# S7CAS-PLEIADES-CARTE-MERE_P06_CLOCK.net
KiCad netlist of a schematic drawn in Altium Designer
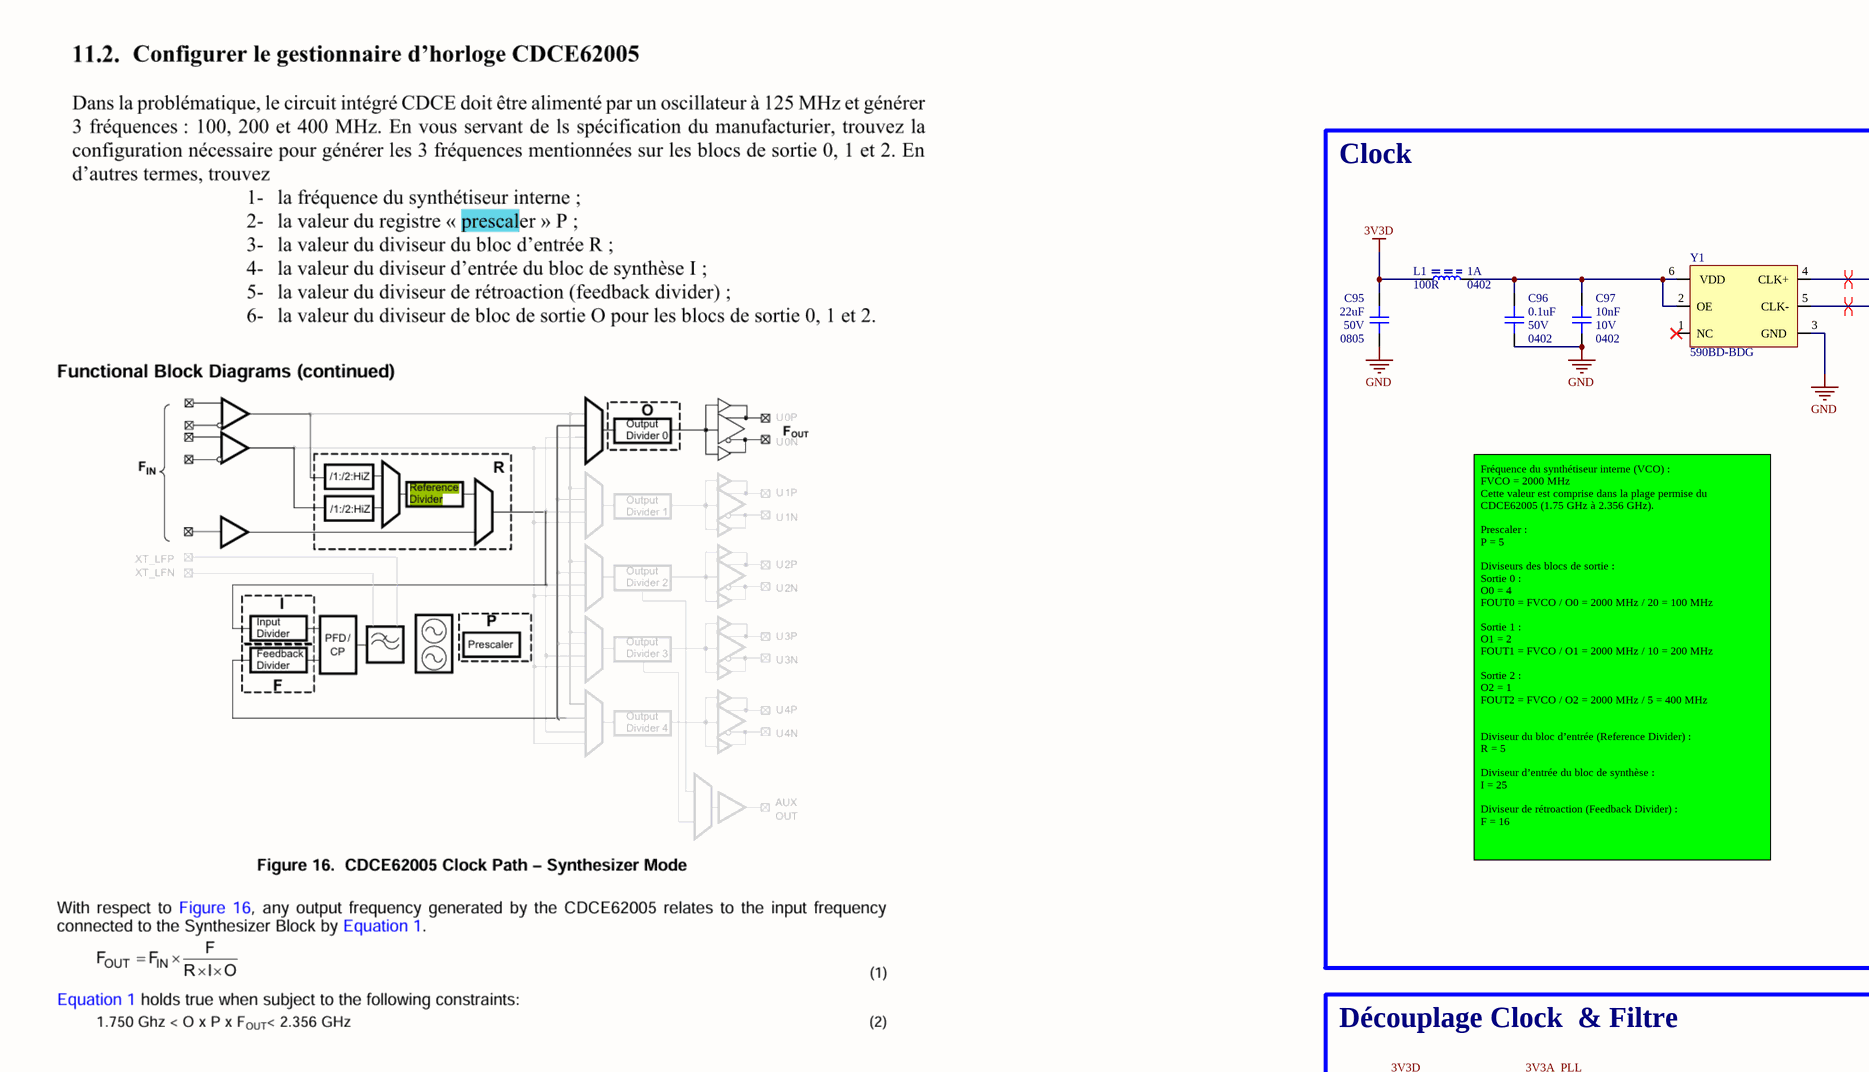
[diagram p0: S7CAS-PLEIADES-CARTE-MERE_P06_CLOCK.SchDoc, top left]
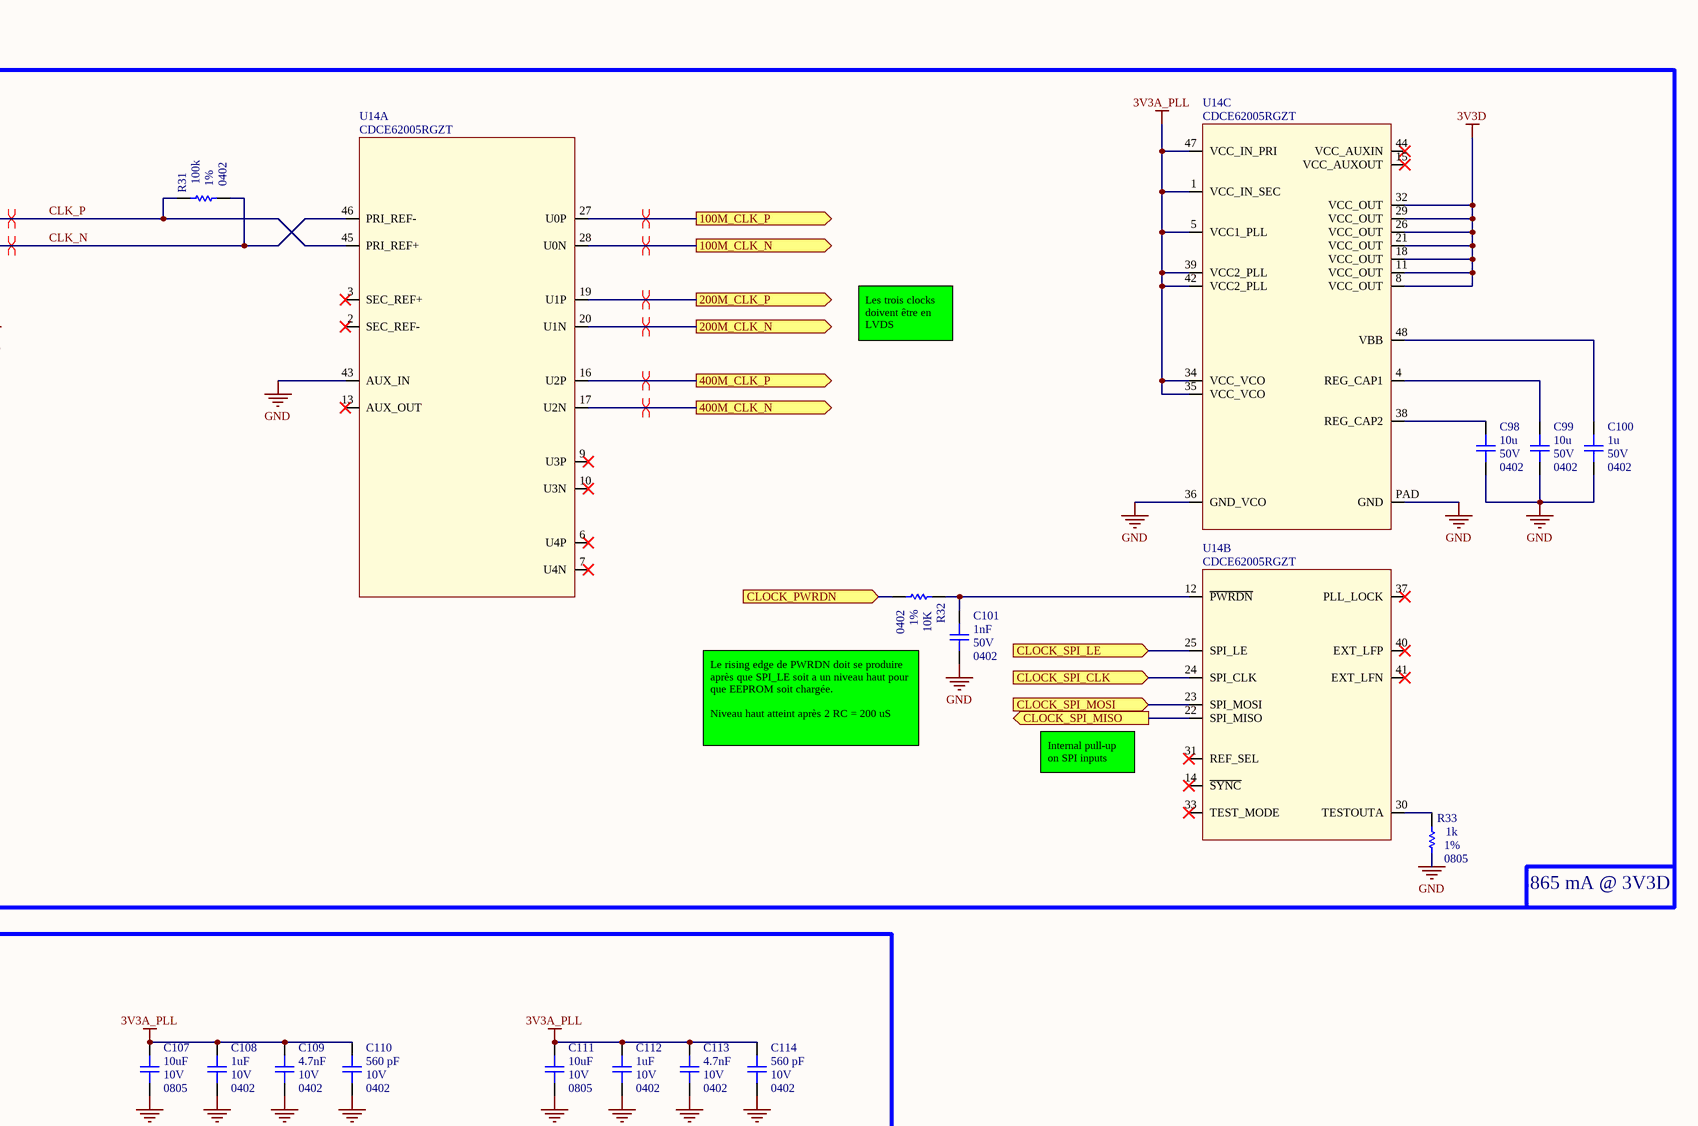
[diagram p1: S7CAS-PLEIADES-CARTE-MERE_P06_CLOCK.SchDoc, top middle]
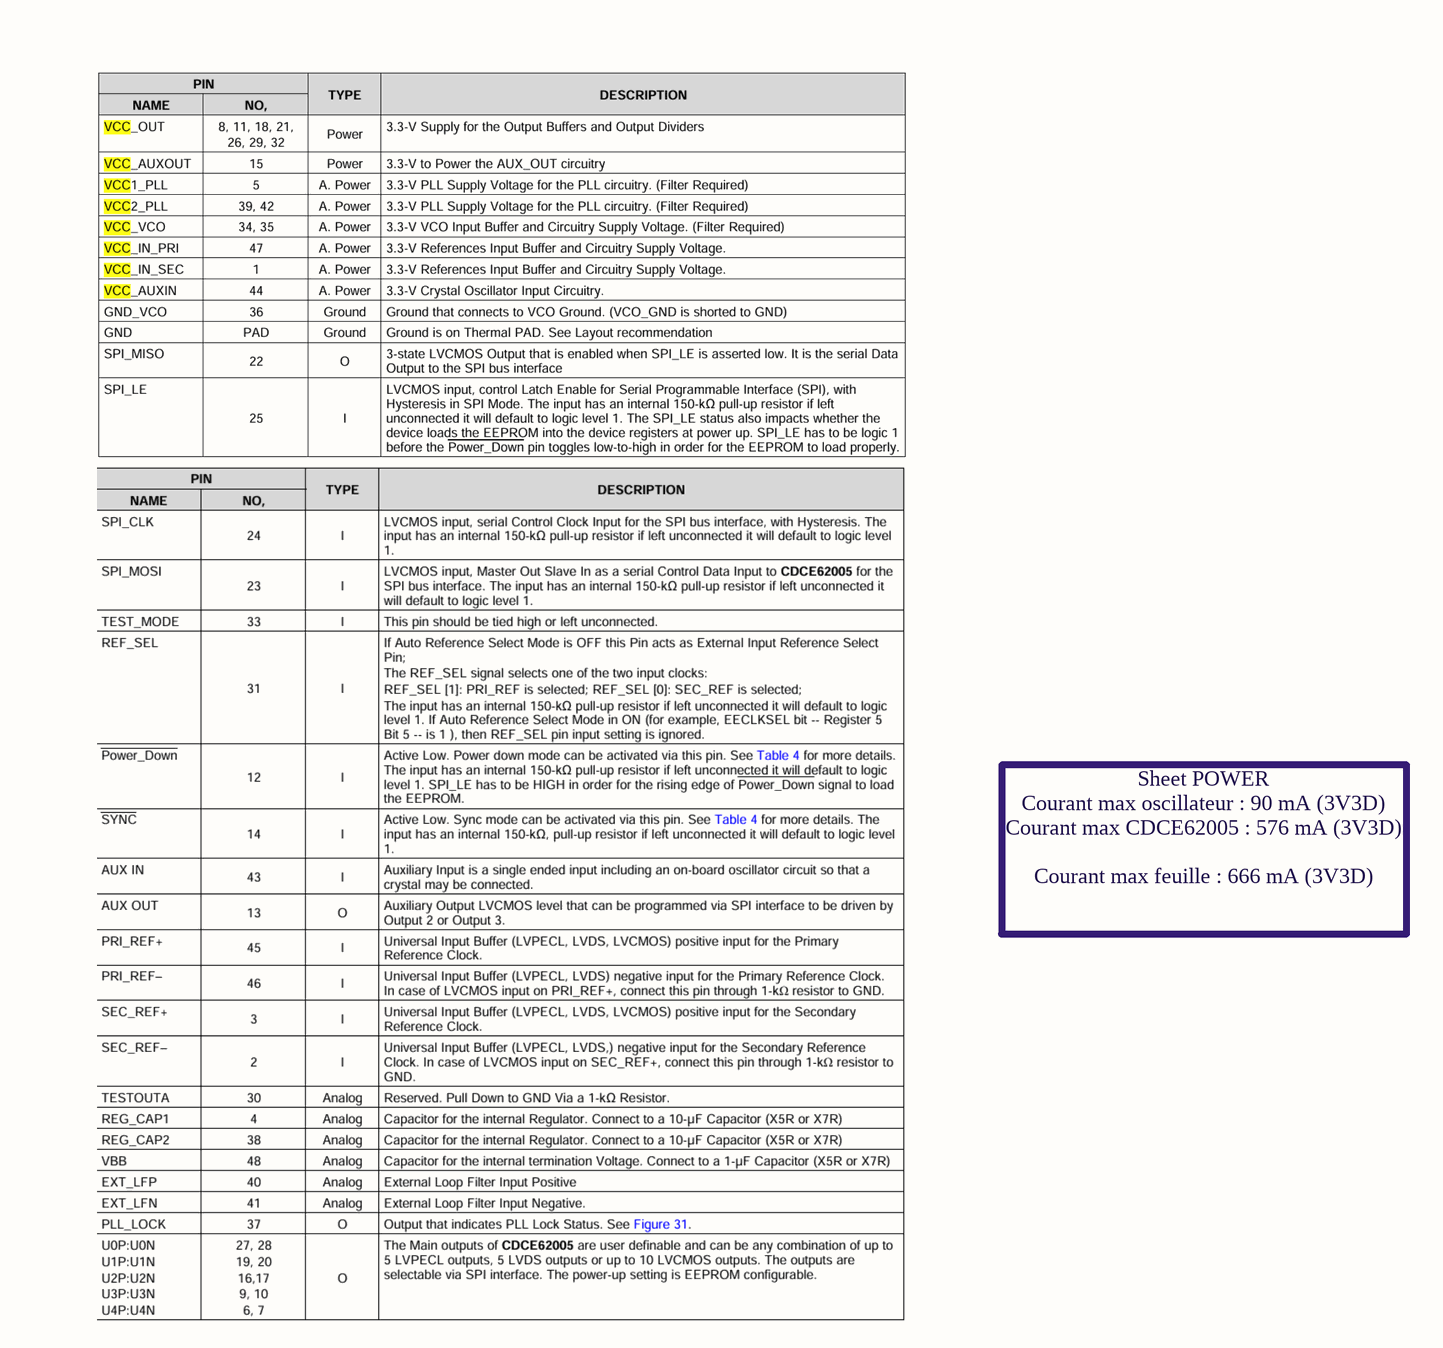
[diagram p2: S7CAS-PLEIADES-CARTE-MERE_P06_CLOCK.SchDoc, top right]
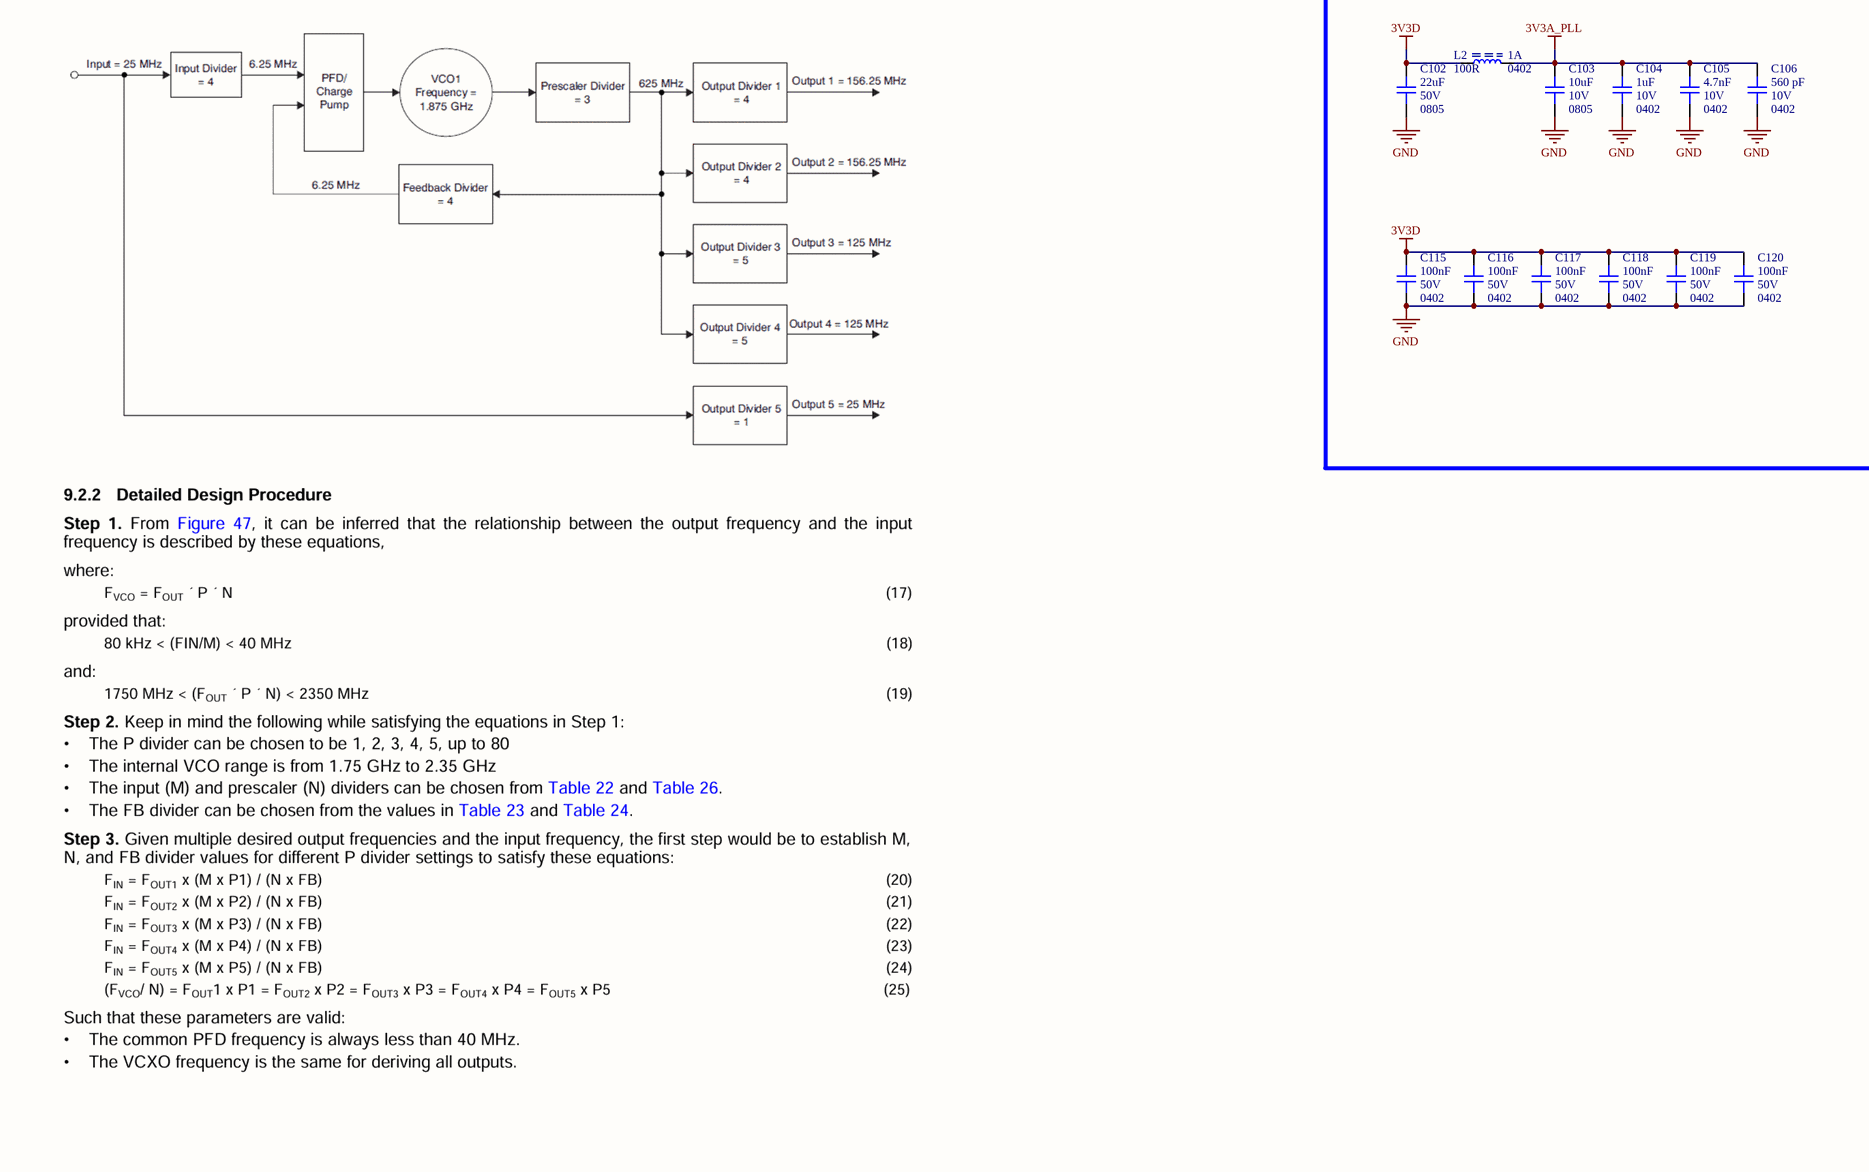
[diagram p3: S7CAS-PLEIADES-CARTE-MERE_P06_CLOCK.SchDoc, bottom left]
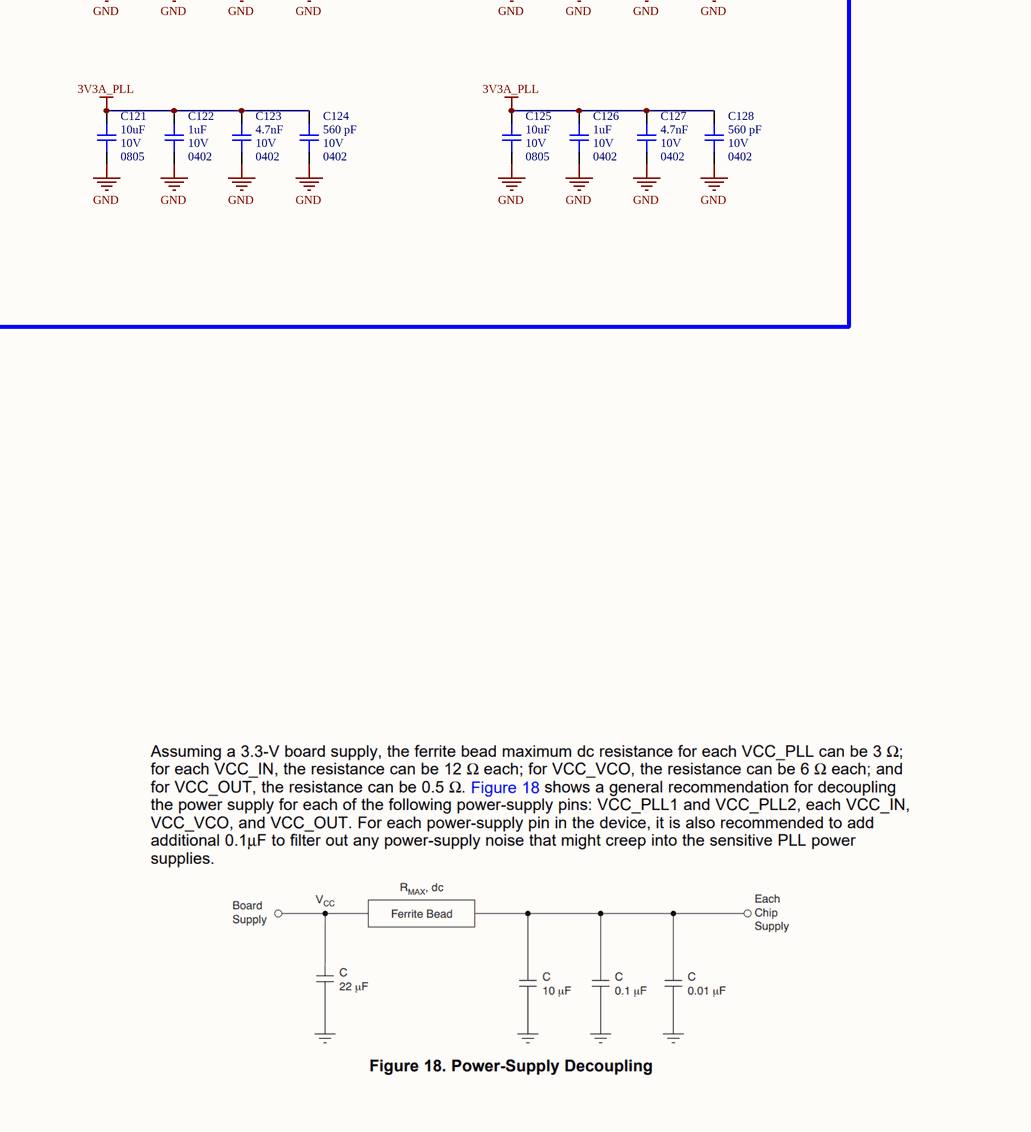
[diagram p4: S7CAS-PLEIADES-CARTE-MERE_P06_CLOCK.SchDoc, bottom middle]

(export (version "E")
  (design (tool "Eeschema 10.0.6"))
  (components
    (comp (ref "C95")
      (value "22uF")
      (footprint "CAP_0805")
      (description "CAP - 0805")
      (fields
        (field (name "VOLTAGE") "50V")
        (field (name "PACKAGE") "0805")
        (field (name "CREATEDBY") "Jonathan Bouchard")
      )
      (libsource (lib "s7cas_lib2023") (part "CAP - 0805"))
    )
    (comp (ref "C96")
      (value "0.1uF")
      (footprint "CAP_0402")
      (description "CAP - 0402")
      (fields
        (field (name "VOLTAGE") "50V")
        (field (name "PACKAGE") "0402")
        (field (name "CREATEDBY") "Jonathan Bouchard")
      )
      (libsource (lib "s7cas_lib2023") (part "CAP - 0402"))
    )
    (comp (ref "C97")
      (value "10nF")
      (footprint "CAP_0402")
      (description "CAP - 0402")
      (fields
        (field (name "VOLTAGE") "10V")
        (field (name "PACKAGE") "0402")
        (field (name "CREATEDBY") "Jonathan Bouchard")
      )
      (libsource (lib "s7cas_lib2023") (part "CAP - 0402"))
    )
    (comp (ref "C98")
      (value "10u")
      (footprint "CAP_0402")
      (description "CAP - 0402")
      (fields
        (field (name "VOLTAGE") "50V")
        (field (name "PACKAGE") "0402")
        (field (name "CREATEDBY") "Jonathan Bouchard")
      )
      (libsource (lib "s7cas_lib2023") (part "CAP - 0402"))
    )
    (comp (ref "C99")
      (value "10u")
      (footprint "CAP_0402")
      (description "CAP - 0402")
      (fields
        (field (name "VOLTAGE") "50V")
        (field (name "PACKAGE") "0402")
        (field (name "CREATEDBY") "Jonathan Bouchard")
      )
      (libsource (lib "s7cas_lib2023") (part "CAP - 0402"))
    )
    (comp (ref "C100")
      (value "1u")
      (footprint "CAP_0402")
      (description "CAP - 0402")
      (fields
        (field (name "VOLTAGE") "50V")
        (field (name "PACKAGE") "0402")
        (field (name "CREATEDBY") "Jonathan Bouchard")
      )
      (libsource (lib "s7cas_lib2023") (part "CAP - 0402"))
    )
    (comp (ref "C101")
      (value "1nF")
      (footprint "CAP_0402")
      (description "CAP - 0402")
      (fields
        (field (name "VOLTAGE") "50V")
        (field (name "PACKAGE") "0402")
        (field (name "CREATEDBY") "Jonathan Bouchard")
      )
      (libsource (lib "s7cas_lib2023") (part "CAP - 0402"))
    )
    (comp (ref "C102")
      (value "22uF")
      (footprint "CAP_0805")
      (description "CAP - 0805")
      (fields
        (field (name "VOLTAGE") "50V")
        (field (name "PACKAGE") "0805")
        (field (name "CREATEDBY") "Jonathan Bouchard")
      )
      (libsource (lib "s7cas_lib2023") (part "CAP - 0805"))
    )
    (comp (ref "C103")
      (value "10uF")
      (footprint "CAP_0805")
      (description "CAP - 0805")
      (fields
        (field (name "VOLTAGE") "10V")
        (field (name "PACKAGE") "0805")
        (field (name "CREATEDBY") "Jonathan Bouchard")
      )
      (libsource (lib "s7cas_lib2023") (part "CAP - 0805"))
    )
    (comp (ref "C104")
      (value "1uF")
      (footprint "CAP_0402")
      (description "CAP - 0402")
      (fields
        (field (name "VOLTAGE") "10V")
        (field (name "PACKAGE") "0402")
        (field (name "CREATEDBY") "Jonathan Bouchard")
      )
      (libsource (lib "s7cas_lib2023") (part "CAP - 0402"))
    )
    (comp (ref "C105")
      (value "4.7nF")
      (footprint "CAP_0402")
      (description "CAP - 0402")
      (fields
        (field (name "VOLTAGE") "10V")
        (field (name "PACKAGE") "0402")
        (field (name "CREATEDBY") "Jonathan Bouchard")
      )
      (libsource (lib "s7cas_lib2023") (part "CAP - 0402"))
    )
    (comp (ref "C106")
      (value "560 pF")
      (footprint "CAP_0402")
      (description "CAP - 0402")
      (fields
        (field (name "VOLTAGE") "10V")
        (field (name "PACKAGE") "0402")
        (field (name "CREATEDBY") "Jonathan Bouchard")
      )
      (libsource (lib "s7cas_lib2023") (part "CAP - 0402"))
    )
    (comp (ref "C107")
      (value "10uF")
      (footprint "CAP_0805")
      (description "CAP - 0805")
      (fields
        (field (name "VOLTAGE") "10V")
        (field (name "PACKAGE") "0805")
        (field (name "CREATEDBY") "Jonathan Bouchard")
      )
      (libsource (lib "s7cas_lib2023") (part "CAP - 0805"))
    )
    (comp (ref "C108")
      (value "1uF")
      (footprint "CAP_0402")
      (description "CAP - 0402")
      (fields
        (field (name "VOLTAGE") "10V")
        (field (name "PACKAGE") "0402")
        (field (name "CREATEDBY") "Jonathan Bouchard")
      )
      (libsource (lib "s7cas_lib2023") (part "CAP - 0402"))
    )
    (comp (ref "C109")
      (value "4.7nF")
      (footprint "CAP_0402")
      (description "CAP - 0402")
      (fields
        (field (name "VOLTAGE") "10V")
        (field (name "PACKAGE") "0402")
        (field (name "CREATEDBY") "Jonathan Bouchard")
      )
      (libsource (lib "s7cas_lib2023") (part "CAP - 0402"))
    )
    (comp (ref "C110")
      (value "560 pF")
      (footprint "CAP_0402")
      (description "CAP - 0402")
      (fields
        (field (name "VOLTAGE") "10V")
        (field (name "PACKAGE") "0402")
        (field (name "CREATEDBY") "Jonathan Bouchard")
      )
      (libsource (lib "s7cas_lib2023") (part "CAP - 0402"))
    )
    (comp (ref "C111")
      (value "10uF")
      (footprint "CAP_0805")
      (description "CAP - 0805")
      (fields
        (field (name "VOLTAGE") "10V")
        (field (name "PACKAGE") "0805")
        (field (name "CREATEDBY") "Jonathan Bouchard")
      )
      (libsource (lib "s7cas_lib2023") (part "CAP - 0805"))
    )
    (comp (ref "C112")
      (value "1uF")
      (footprint "CAP_0402")
      (description "CAP - 0402")
      (fields
        (field (name "VOLTAGE") "10V")
        (field (name "PACKAGE") "0402")
        (field (name "CREATEDBY") "Jonathan Bouchard")
      )
      (libsource (lib "s7cas_lib2023") (part "CAP - 0402"))
    )
    (comp (ref "C113")
      (value "4.7nF")
      (footprint "CAP_0402")
      (description "CAP - 0402")
      (fields
        (field (name "VOLTAGE") "10V")
        (field (name "PACKAGE") "0402")
        (field (name "CREATEDBY") "Jonathan Bouchard")
      )
      (libsource (lib "s7cas_lib2023") (part "CAP - 0402"))
    )
    (comp (ref "C114")
      (value "560 pF")
      (footprint "CAP_0402")
      (description "CAP - 0402")
      (fields
        (field (name "VOLTAGE") "10V")
        (field (name "PACKAGE") "0402")
        (field (name "CREATEDBY") "Jonathan Bouchard")
      )
      (libsource (lib "s7cas_lib2023") (part "CAP - 0402"))
    )
    (comp (ref "C115")
      (value "100nF")
      (footprint "CAP_0402")
      (description "CAP - 0402")
      (fields
        (field (name "VOLTAGE") "50V")
        (field (name "PACKAGE") "0402")
        (field (name "CREATEDBY") "Jonathan Bouchard")
      )
      (libsource (lib "s7cas_lib2023") (part "CAP - 0402"))
    )
    (comp (ref "C116")
      (value "100nF")
      (footprint "CAP_0402")
      (description "CAP - 0402")
      (fields
        (field (name "VOLTAGE") "50V")
        (field (name "PACKAGE") "0402")
        (field (name "CREATEDBY") "Jonathan Bouchard")
      )
      (libsource (lib "s7cas_lib2023") (part "CAP - 0402"))
    )
    (comp (ref "C117")
      (value "100nF")
      (footprint "CAP_0402")
      (description "CAP - 0402")
      (fields
        (field (name "VOLTAGE") "50V")
        (field (name "PACKAGE") "0402")
        (field (name "CREATEDBY") "Jonathan Bouchard")
      )
      (libsource (lib "s7cas_lib2023") (part "CAP - 0402"))
    )
    (comp (ref "C118")
      (value "100nF")
      (footprint "CAP_0402")
      (description "CAP - 0402")
      (fields
        (field (name "VOLTAGE") "50V")
        (field (name "PACKAGE") "0402")
        (field (name "CREATEDBY") "Jonathan Bouchard")
      )
      (libsource (lib "s7cas_lib2023") (part "CAP - 0402"))
    )
    (comp (ref "C119")
      (value "100nF")
      (footprint "CAP_0402")
      (description "CAP - 0402")
      (fields
        (field (name "VOLTAGE") "50V")
        (field (name "PACKAGE") "0402")
        (field (name "CREATEDBY") "Jonathan Bouchard")
      )
      (libsource (lib "s7cas_lib2023") (part "CAP - 0402"))
    )
    (comp (ref "C120")
      (value "100nF")
      (footprint "CAP_0402")
      (description "CAP - 0402")
      (fields
        (field (name "VOLTAGE") "50V")
        (field (name "PACKAGE") "0402")
        (field (name "CREATEDBY") "Jonathan Bouchard")
      )
      (libsource (lib "s7cas_lib2023") (part "CAP - 0402"))
    )
    (comp (ref "C121")
      (value "10uF")
      (footprint "CAP_0805")
      (description "CAP - 0805")
      (fields
        (field (name "VOLTAGE") "10V")
        (field (name "PACKAGE") "0805")
        (field (name "CREATEDBY") "Jonathan Bouchard")
      )
      (libsource (lib "s7cas_lib2023") (part "CAP - 0805"))
    )
    (comp (ref "C122")
      (value "1uF")
      (footprint "CAP_0402")
      (description "CAP - 0402")
      (fields
        (field (name "VOLTAGE") "10V")
        (field (name "PACKAGE") "0402")
        (field (name "CREATEDBY") "Jonathan Bouchard")
      )
      (libsource (lib "s7cas_lib2023") (part "CAP - 0402"))
    )
    (comp (ref "C123")
      (value "4.7nF")
      (footprint "CAP_0402")
      (description "CAP - 0402")
      (fields
        (field (name "VOLTAGE") "10V")
        (field (name "PACKAGE") "0402")
        (field (name "CREATEDBY") "Jonathan Bouchard")
      )
      (libsource (lib "s7cas_lib2023") (part "CAP - 0402"))
    )
    (comp (ref "C124")
      (value "560 pF")
      (footprint "CAP_0402")
      (description "CAP - 0402")
      (fields
        (field (name "VOLTAGE") "10V")
        (field (name "PACKAGE") "0402")
        (field (name "CREATEDBY") "Jonathan Bouchard")
      )
      (libsource (lib "s7cas_lib2023") (part "CAP - 0402"))
    )
    (comp (ref "C125")
      (value "10uF")
      (footprint "CAP_0805")
      (description "CAP - 0805")
      (fields
        (field (name "VOLTAGE") "10V")
        (field (name "PACKAGE") "0805")
        (field (name "CREATEDBY") "Jonathan Bouchard")
      )
      (libsource (lib "s7cas_lib2023") (part "CAP - 0805"))
    )
    (comp (ref "C126")
      (value "1uF")
      (footprint "CAP_0402")
      (description "CAP - 0402")
      (fields
        (field (name "VOLTAGE") "10V")
        (field (name "PACKAGE") "0402")
        (field (name "CREATEDBY") "Jonathan Bouchard")
      )
      (libsource (lib "s7cas_lib2023") (part "CAP - 0402"))
    )
    (comp (ref "C127")
      (value "4.7nF")
      (footprint "CAP_0402")
      (description "CAP - 0402")
      (fields
        (field (name "VOLTAGE") "10V")
        (field (name "PACKAGE") "0402")
        (field (name "CREATEDBY") "Jonathan Bouchard")
      )
      (libsource (lib "s7cas_lib2023") (part "CAP - 0402"))
    )
    (comp (ref "C128")
      (value "560 pF")
      (footprint "CAP_0402")
      (description "CAP - 0402")
      (fields
        (field (name "VOLTAGE") "10V")
        (field (name "PACKAGE") "0402")
        (field (name "CREATEDBY") "Jonathan Bouchard")
      )
      (libsource (lib "s7cas_lib2023") (part "CAP - 0402"))
    )
    (comp (ref "L1")
      (value "100R")
      (footprint "FER_0402")
      (description "FER - 0402")
      (fields
        (field (name "CURRENT") "1A")
        (field (name "PACKAGE") "0402")
        (field (name "CREATEDBY") "Jonathan Bouchard")
      )
      (libsource (lib "s7cas_lib2023") (part "FER - 0402"))
    )
    (comp (ref "L2")
      (value "100R")
      (footprint "FER_0402")
      (description "FER - 0402")
      (fields
        (field (name "CURRENT") "1A")
        (field (name "PACKAGE") "0402")
        (field (name "CREATEDBY") "Jonathan Bouchard")
      )
      (libsource (lib "s7cas_lib2023") (part "FER - 0402"))
    )
    (comp (ref "R31")
      (value "100k")
      (footprint "RES_0402")
      (description "RES - 0402")
      (fields
        (field (name "VOLTAGE") "50V")
        (field (name "POWER") "1/16W")
        (field (name "PACKAGE") "0402")
        (field (name "PRECISION") "1%")
        (field (name "CREATEDBY") "Jonathan Bouchard")
      )
      (libsource (lib "s7cas_lib2023") (part "RES - 0402"))
    )
    (comp (ref "R32")
      (value "10K")
      (footprint "RES_0402")
      (description "RES - 0402")
      (fields
        (field (name "VOLTAGE") "50V")
        (field (name "POWER") "1/16W")
        (field (name "PACKAGE") "0402")
        (field (name "PRECISION") "1%")
        (field (name "CREATEDBY") "Jonathan Bouchard")
      )
      (libsource (lib "s7cas_lib2023") (part "RES - 0402"))
    )
    (comp (ref "R33")
      (value "1k")
      (footprint "RES_0805")
      (description "RES - 0805")
      (fields
        (field (name "PACKAGE") "0805")
        (field (name "PRECISION") "1%")
        (field (name "CREATEDBY") "Jonathan Bouchard")
      )
      (libsource (lib "s7cas_lib2023") (part "RES - 0805"))
    )
    (comp (ref "U14")
      (value "CDCE62005RGZT")
      (footprint "TIM_CDCE62005RGZT")
      (description "TIM - CLK SYNTH JITTER CLEANER 3:5 - QFN-48")
      (fields
        (field (name "VOLTAGE") "3 V ~ 3.6 V")
        (field (name "MFG") "Texas Instruments")
        (field (name "CREATEDBY") "Jonathan Bouchard")
      )
      (libsource (lib "s7cas_lib2023") (part "TIM_CDCE62005RGZT"))
    )
    (comp (ref "Y1")
      (value "590BD-BDG")
      (footprint "OSC_590BD-BDG")
      (description "TIM - OSC PROG 125MHz ~ 214.999MHz LVDS 3.3V 7PPM EN/DS - 6-SMD")
      (fields
        (field (name "CREATEDBY/DATE") "from 590BD-CDG")
        (field (name "VERIFIEDBY") "Caroline Paulin / 3/10/2019")
      )
      (libsource (lib "s7cas_lib2023") (part "OSC_590BD-BDG"))
    )
  )
  (nets
    (net (code "1") (name "/100M_CLK_N") (class "Default")
      (node (ref "U14") (pin "28") (pinfunction "U0N_28") (pintype "passive"))
    )
    (net (code "2") (name "/100M_CLK_P") (class "Default")
      (node (ref "U14") (pin "27") (pinfunction "U0P_27") (pintype "passive"))
    )
    (net (code "3") (name "/200M_CLK_N") (class "Default")
      (node (ref "U14") (pin "20") (pinfunction "U1N_20") (pintype "passive"))
    )
    (net (code "4") (name "/200M_CLK_P") (class "Default")
      (node (ref "U14") (pin "19") (pinfunction "U1P_19") (pintype "passive"))
    )
    (net (code "5") (name "/400M_CLK_N") (class "Default")
      (node (ref "U14") (pin "17") (pinfunction "U2N_17") (pintype "passive"))
    )
    (net (code "6") (name "/400M_CLK_P") (class "Default")
      (node (ref "U14") (pin "16") (pinfunction "U2P_16") (pintype "passive"))
    )
    (net (code "7") (name "/CLK_N") (class "Default")
      (node (ref "R31") (pin "1") (pinfunction "1_1") (pintype "passive"))
      (node (ref "U14") (pin "46") (pinfunction "PRI_REF-_46") (pintype "passive"))
      (node (ref "Y1") (pin "5") (pinfunction "CLK-_5") (pintype "passive"))
    )
    (net (code "8") (name "/CLK_P") (class "Default")
      (node (ref "R31") (pin "2") (pinfunction "2_2") (pintype "passive"))
      (node (ref "U14") (pin "45") (pinfunction "PRI_REF+_45") (pintype "passive"))
      (node (ref "Y1") (pin "4") (pinfunction "CLK+_4") (pintype "passive"))
    )
    (net (code "9") (name "/CLOCK_PWRDN") (class "Default")
      (node (ref "R32") (pin "1") (pinfunction "1_1") (pintype "passive"))
    )
    (net (code "10") (name "/CLOCK_SPI_CLK") (class "Default")
      (node (ref "U14") (pin "24") (pinfunction "SPI_CLK_24") (pintype "passive"))
    )
    (net (code "11") (name "/CLOCK_SPI_LE") (class "Default")
      (node (ref "U14") (pin "25") (pinfunction "SPI_LE_25") (pintype "passive"))
    )
    (net (code "12") (name "/CLOCK_SPI_MISO") (class "Default")
      (node (ref "U14") (pin "22") (pinfunction "SPI_MISO_22") (pintype "passive"))
    )
    (net (code "13") (name "/CLOCK_SPI_MOSI") (class "Default")
      (node (ref "U14") (pin "23") (pinfunction "SPI_MOSI_23") (pintype "passive"))
    )
    (net (code "14") (name "3V3A_PLL") (class "Default")
      (node (ref "C103") (pin "2") (pinfunction "2_2") (pintype "passive"))
      (node (ref "C104") (pin "2") (pinfunction "2_2") (pintype "passive"))
      (node (ref "C105") (pin "2") (pinfunction "2_2") (pintype "passive"))
      (node (ref "C106") (pin "2") (pinfunction "2_2") (pintype "passive"))
      (node (ref "C107") (pin "2") (pinfunction "2_2") (pintype "passive"))
      (node (ref "C108") (pin "2") (pinfunction "2_2") (pintype "passive"))
      (node (ref "C109") (pin "2") (pinfunction "2_2") (pintype "passive"))
      (node (ref "C110") (pin "2") (pinfunction "2_2") (pintype "passive"))
      (node (ref "C111") (pin "2") (pinfunction "2_2") (pintype "passive"))
      (node (ref "C112") (pin "2") (pinfunction "2_2") (pintype "passive"))
      (node (ref "C113") (pin "2") (pinfunction "2_2") (pintype "passive"))
      (node (ref "C114") (pin "2") (pinfunction "2_2") (pintype "passive"))
      (node (ref "C121") (pin "2") (pinfunction "2_2") (pintype "passive"))
      (node (ref "C122") (pin "2") (pinfunction "2_2") (pintype "passive"))
      (node (ref "C123") (pin "2") (pinfunction "2_2") (pintype "passive"))
      (node (ref "C124") (pin "2") (pinfunction "2_2") (pintype "passive"))
      (node (ref "C125") (pin "2") (pinfunction "2_2") (pintype "passive"))
      (node (ref "C126") (pin "2") (pinfunction "2_2") (pintype "passive"))
      (node (ref "C127") (pin "2") (pinfunction "2_2") (pintype "passive"))
      (node (ref "C128") (pin "2") (pinfunction "2_2") (pintype "passive"))
      (node (ref "L2") (pin "1") (pinfunction "1_1") (pintype "passive"))
      (node (ref "U14") (pin "1") (pinfunction "VCC_IN_SEC_1") (pintype "passive"))
      (node (ref "U14") (pin "34") (pinfunction "VCC_VCO_34") (pintype "passive"))
      (node (ref "U14") (pin "35") (pinfunction "VCC_VCO_35") (pintype "passive"))
      (node (ref "U14") (pin "39") (pinfunction "VCC2_PLL_39") (pintype "passive"))
      (node (ref "U14") (pin "42") (pinfunction "VCC2_PLL_42") (pintype "passive"))
      (node (ref "U14") (pin "47") (pinfunction "VCC_IN_PRI_47") (pintype "passive"))
      (node (ref "U14") (pin "5") (pinfunction "VCC1_PLL_5") (pintype "passive"))
    )
    (net (code "15") (name "3V3D") (class "Default")
      (node (ref "C102") (pin "2") (pinfunction "2_2") (pintype "passive"))
      (node (ref "C115") (pin "2") (pinfunction "2_2") (pintype "passive"))
      (node (ref "C116") (pin "2") (pinfunction "2_2") (pintype "passive"))
      (node (ref "C117") (pin "2") (pinfunction "2_2") (pintype "passive"))
      (node (ref "C118") (pin "2") (pinfunction "2_2") (pintype "passive"))
      (node (ref "C119") (pin "2") (pinfunction "2_2") (pintype "passive"))
      (node (ref "C120") (pin "2") (pinfunction "2_2") (pintype "passive"))
      (node (ref "C95") (pin "2") (pinfunction "2_2") (pintype "passive"))
      (node (ref "L1") (pin "2") (pinfunction "2_2") (pintype "passive"))
      (node (ref "L2") (pin "2") (pinfunction "2_2") (pintype "passive"))
      (node (ref "U14") (pin "11") (pinfunction "VCC_OUT_11") (pintype "passive"))
      (node (ref "U14") (pin "18") (pinfunction "VCC_OUT_18") (pintype "passive"))
      (node (ref "U14") (pin "21") (pinfunction "VCC_OUT_21") (pintype "passive"))
      (node (ref "U14") (pin "26") (pinfunction "VCC_OUT_26") (pintype "passive"))
      (node (ref "U14") (pin "29") (pinfunction "VCC_OUT_29") (pintype "passive"))
      (node (ref "U14") (pin "32") (pinfunction "VCC_OUT_32") (pintype "passive"))
      (node (ref "U14") (pin "8") (pinfunction "VCC_OUT_8") (pintype "passive"))
    )
    (net (code "16") (name "GND") (class "Default")
      (node (ref "C100") (pin "1") (pinfunction "1_1") (pintype "passive"))
      (node (ref "C101") (pin "1") (pinfunction "1_1") (pintype "passive"))
      (node (ref "C102") (pin "1") (pinfunction "1_1") (pintype "passive"))
      (node (ref "C103") (pin "1") (pinfunction "1_1") (pintype "passive"))
      (node (ref "C104") (pin "1") (pinfunction "1_1") (pintype "passive"))
      (node (ref "C105") (pin "1") (pinfunction "1_1") (pintype "passive"))
      (node (ref "C106") (pin "1") (pinfunction "1_1") (pintype "passive"))
      (node (ref "C107") (pin "1") (pinfunction "1_1") (pintype "passive"))
      (node (ref "C108") (pin "1") (pinfunction "1_1") (pintype "passive"))
      (node (ref "C109") (pin "1") (pinfunction "1_1") (pintype "passive"))
      (node (ref "C110") (pin "1") (pinfunction "1_1") (pintype "passive"))
      (node (ref "C111") (pin "1") (pinfunction "1_1") (pintype "passive"))
      (node (ref "C112") (pin "1") (pinfunction "1_1") (pintype "passive"))
      (node (ref "C113") (pin "1") (pinfunction "1_1") (pintype "passive"))
      (node (ref "C114") (pin "1") (pinfunction "1_1") (pintype "passive"))
      (node (ref "C115") (pin "1") (pinfunction "1_1") (pintype "passive"))
      (node (ref "C116") (pin "1") (pinfunction "1_1") (pintype "passive"))
      (node (ref "C117") (pin "1") (pinfunction "1_1") (pintype "passive"))
      (node (ref "C118") (pin "1") (pinfunction "1_1") (pintype "passive"))
      (node (ref "C119") (pin "1") (pinfunction "1_1") (pintype "passive"))
      (node (ref "C120") (pin "1") (pinfunction "1_1") (pintype "passive"))
      (node (ref "C121") (pin "1") (pinfunction "1_1") (pintype "passive"))
      (node (ref "C122") (pin "1") (pinfunction "1_1") (pintype "passive"))
      (node (ref "C123") (pin "1") (pinfunction "1_1") (pintype "passive"))
      (node (ref "C124") (pin "1") (pinfunction "1_1") (pintype "passive"))
      (node (ref "C125") (pin "1") (pinfunction "1_1") (pintype "passive"))
      (node (ref "C126") (pin "1") (pinfunction "1_1") (pintype "passive"))
      (node (ref "C127") (pin "1") (pinfunction "1_1") (pintype "passive"))
      (node (ref "C128") (pin "1") (pinfunction "1_1") (pintype "passive"))
      (node (ref "C95") (pin "1") (pinfunction "1_1") (pintype "passive"))
      (node (ref "C96") (pin "1") (pinfunction "1_1") (pintype "passive"))
      (node (ref "C97") (pin "1") (pinfunction "1_1") (pintype "passive"))
      (node (ref "C98") (pin "1") (pinfunction "1_1") (pintype "passive"))
      (node (ref "C99") (pin "1") (pinfunction "1_1") (pintype "passive"))
      (node (ref "R33") (pin "1") (pinfunction "1_1") (pintype "passive"))
      (node (ref "U14") (pin "36") (pinfunction "GND_VCO_36") (pintype "passive"))
      (node (ref "U14") (pin "43") (pinfunction "AUX_IN_43") (pintype "passive"))
      (node (ref "U14") (pin "PAD") (pinfunction "GND_PAD") (pintype "passive"))
      (node (ref "Y1") (pin "3") (pinfunction "GND_3") (pintype "passive"))
    )
    (net (code "17") (name "Net-(U14B-TESTOUTA)") (class "Default")
      (node (ref "R33") (pin "2") (pinfunction "2_2") (pintype "passive"))
      (node (ref "U14") (pin "30") (pinfunction "TESTOUTA_30") (pintype "passive"))
    )
    (net (code "18") (name "Net-(U14B-~{PWRDN})") (class "Default")
      (node (ref "C101") (pin "2") (pinfunction "2_2") (pintype "passive"))
      (node (ref "R32") (pin "2") (pinfunction "2_2") (pintype "passive"))
      (node (ref "U14") (pin "12") (pinfunction "~{PWRDN}_12") (pintype "passive"))
    )
    (net (code "19") (name "Net-(U14C-REG_CAP1)") (class "Default")
      (node (ref "C99") (pin "2") (pinfunction "2_2") (pintype "passive"))
      (node (ref "U14") (pin "4") (pinfunction "REG_CAP1_4") (pintype "passive"))
    )
    (net (code "20") (name "Net-(U14C-REG_CAP2)") (class "Default")
      (node (ref "C98") (pin "2") (pinfunction "2_2") (pintype "passive"))
      (node (ref "U14") (pin "38") (pinfunction "REG_CAP2_38") (pintype "passive"))
    )
    (net (code "21") (name "Net-(U14C-VBB)") (class "Default")
      (node (ref "C100") (pin "2") (pinfunction "2_2") (pintype "passive"))
      (node (ref "U14") (pin "48") (pinfunction "VBB_48") (pintype "passive"))
    )
    (net (code "22") (name "Net-(Y1-OE)") (class "Default")
      (node (ref "C96") (pin "2") (pinfunction "2_2") (pintype "passive"))
      (node (ref "C97") (pin "2") (pinfunction "2_2") (pintype "passive"))
      (node (ref "L1") (pin "1") (pinfunction "1_1") (pintype "passive"))
      (node (ref "Y1") (pin "2") (pinfunction "OE_2") (pintype "passive"))
      (node (ref "Y1") (pin "6") (pinfunction "VDD_6") (pintype "passive"))
    )
    (net (code "23") (name "unconnected-(U14A-AUX_OUT-Pad13)") (class "Default")
      (node (ref "U14") (pin "13") (pinfunction "AUX_OUT_13") (pintype "passive+no_connect"))
    )
    (net (code "24") (name "unconnected-(U14A-SEC_REF+-Pad3)") (class "Default")
      (node (ref "U14") (pin "3") (pinfunction "SEC_REF+_3") (pintype "passive+no_connect"))
    )
    (net (code "25") (name "unconnected-(U14A-SEC_REF--Pad2)") (class "Default")
      (node (ref "U14") (pin "2") (pinfunction "SEC_REF-_2") (pintype "passive+no_connect"))
    )
    (net (code "26") (name "unconnected-(U14A-U3N-Pad10)") (class "Default")
      (node (ref "U14") (pin "10") (pinfunction "U3N_10") (pintype "passive+no_connect"))
    )
    (net (code "27") (name "unconnected-(U14A-U3P-Pad9)") (class "Default")
      (node (ref "U14") (pin "9") (pinfunction "U3P_9") (pintype "passive+no_connect"))
    )
    (net (code "28") (name "unconnected-(U14A-U4N-Pad7)") (class "Default")
      (node (ref "U14") (pin "7") (pinfunction "U4N_7") (pintype "passive+no_connect"))
    )
    (net (code "29") (name "unconnected-(U14A-U4P-Pad6)") (class "Default")
      (node (ref "U14") (pin "6") (pinfunction "U4P_6") (pintype "passive+no_connect"))
    )
    (net (code "30") (name "unconnected-(U14B-EXT_LFN-Pad41)") (class "Default")
      (node (ref "U14") (pin "41") (pinfunction "EXT_LFN_41") (pintype "passive+no_connect"))
    )
    (net (code "31") (name "unconnected-(U14B-EXT_LFP-Pad40)") (class "Default")
      (node (ref "U14") (pin "40") (pinfunction "EXT_LFP_40") (pintype "passive+no_connect"))
    )
    (net (code "32") (name "unconnected-(U14B-PLL_LOCK-Pad37)") (class "Default")
      (node (ref "U14") (pin "37") (pinfunction "PLL_LOCK_37") (pintype "passive+no_connect"))
    )
    (net (code "33") (name "unconnected-(U14B-REF_SEL-Pad31)") (class "Default")
      (node (ref "U14") (pin "31") (pinfunction "REF_SEL_31") (pintype "passive+no_connect"))
    )
    (net (code "34") (name "unconnected-(U14B-TEST_MODE-Pad33)") (class "Default")
      (node (ref "U14") (pin "33") (pinfunction "TEST_MODE_33") (pintype "passive+no_connect"))
    )
    (net (code "35") (name "unconnected-(U14B-~{SYNC}-Pad14)") (class "Default")
      (node (ref "U14") (pin "14") (pinfunction "~{SYNC}_14") (pintype "passive+no_connect"))
    )
    (net (code "36") (name "unconnected-(U14C-VCC_AUXIN-Pad44)") (class "Default")
      (node (ref "U14") (pin "44") (pinfunction "VCC_AUXIN_44") (pintype "passive+no_connect"))
    )
    (net (code "37") (name "unconnected-(U14C-VCC_AUXOUT-Pad15)") (class "Default")
      (node (ref "U14") (pin "15") (pinfunction "VCC_AUXOUT_15") (pintype "passive+no_connect"))
    )
    (net (code "38") (name "unconnected-(Y1-NC-Pad1)") (class "Default")
      (node (ref "Y1") (pin "1") (pinfunction "NC_1") (pintype "passive+no_connect"))
    )
  )
)
